# MCU_STM32F446RE.net
KiCad netlist of a schematic drawn in Altium Designer
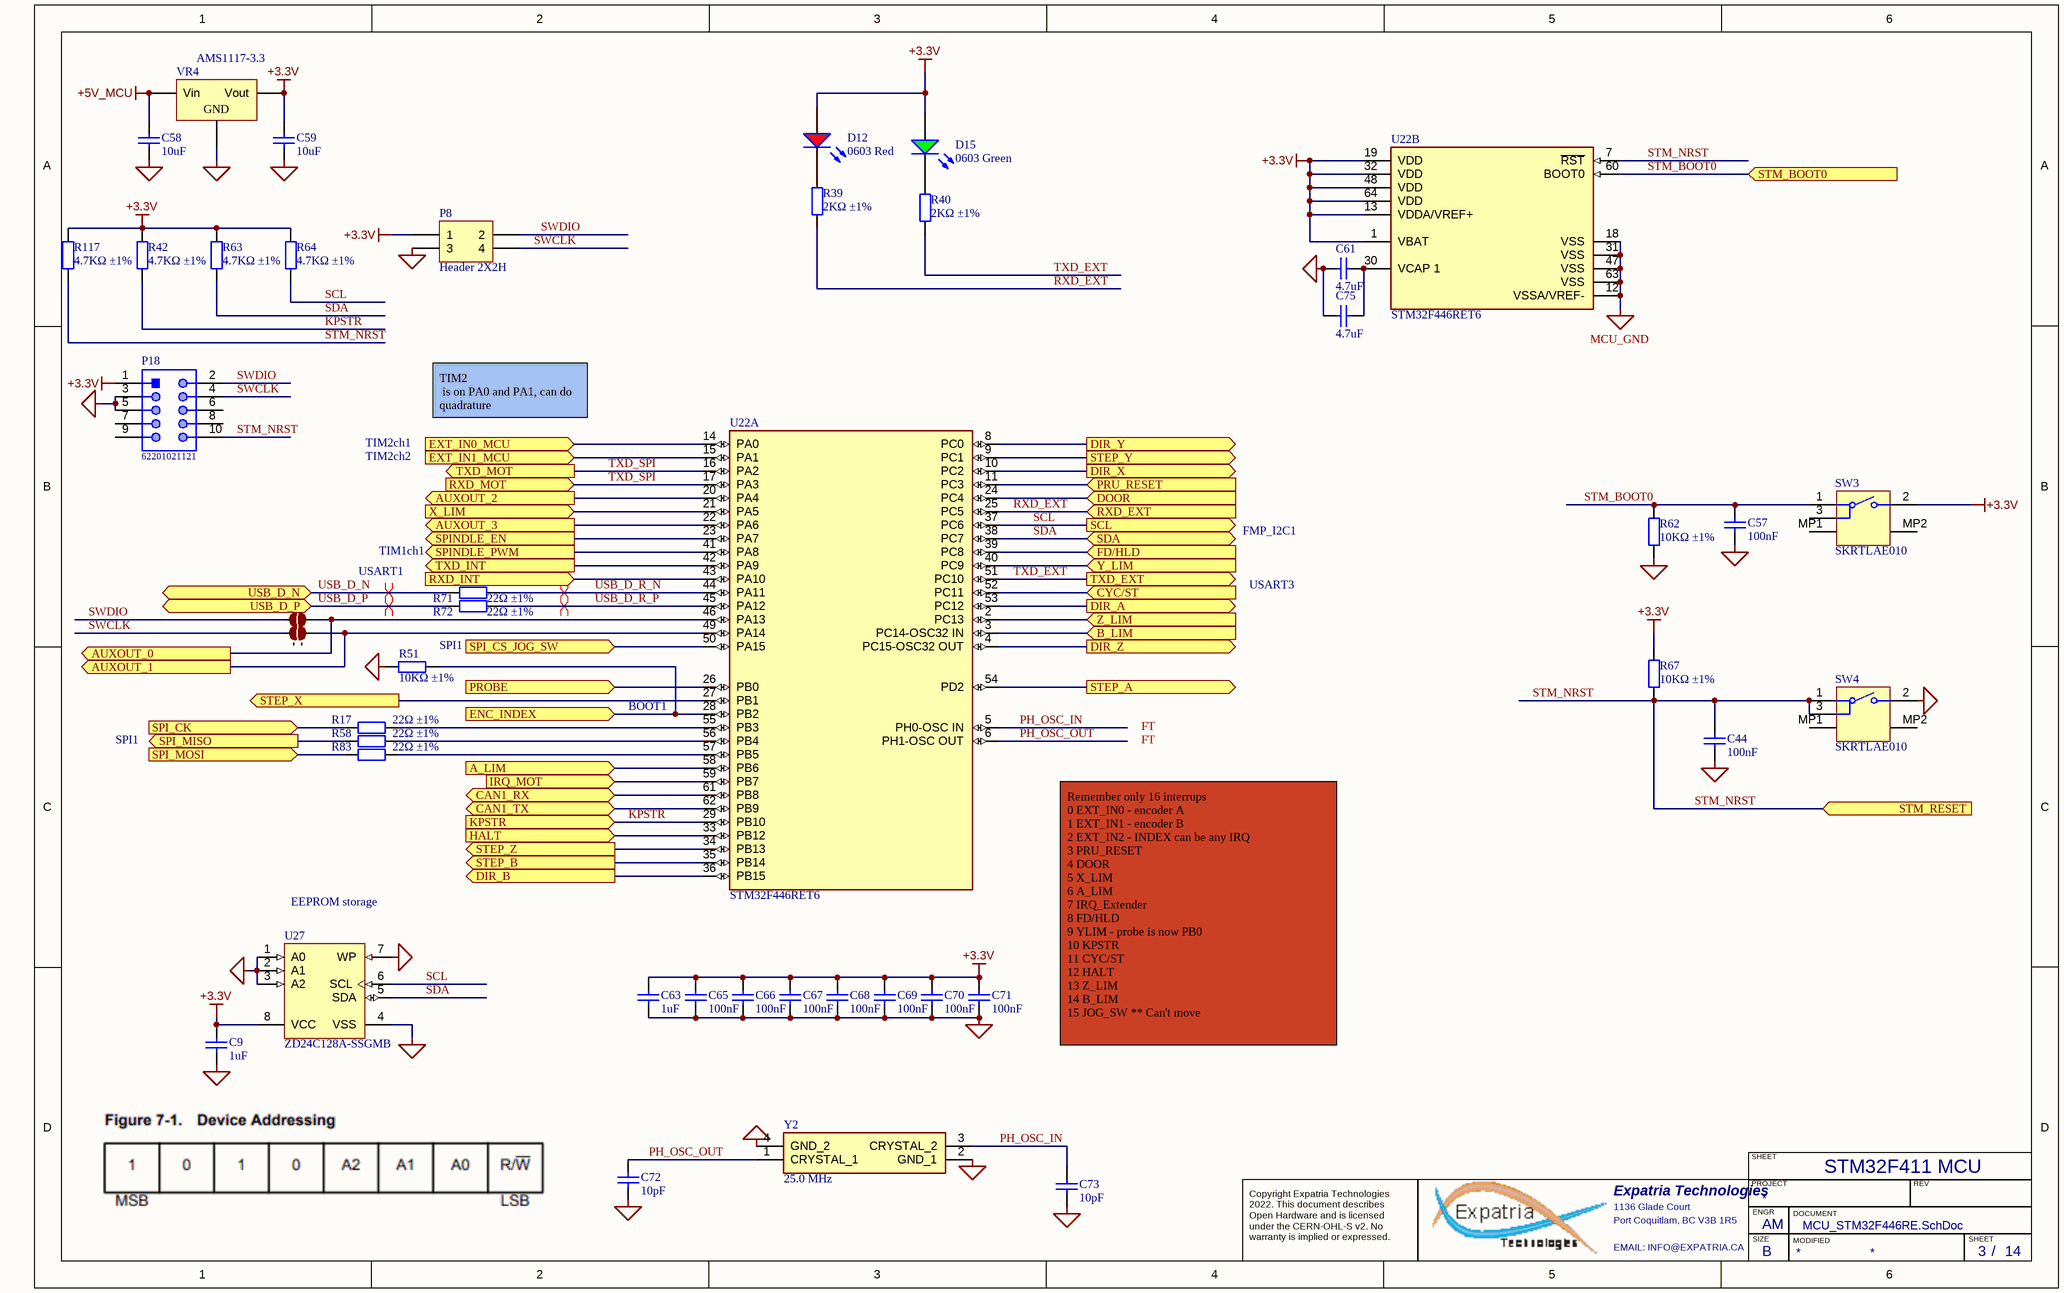
[diagram p0: MCU_STM32F446RE.SchDoc]

(export (version "E")
  (design (tool "Eeschema 10.0.6"))
  (components
    (comp (ref "C9")
      (value "1uF")
      (footprint "0603_C")
      (description "Chip capacitors")
      (fields
        (field (name "MANUFACTURER") "Samsung Electro-Mechanics")
        (field (name "PARTNUMBER") "CL10A105KB8NNNC")
      )
      (libsource (lib "Cap") (part "0603 1uF (105) 10% 50V"))
    )
    (comp (ref "C44")
      (value "100nF")
      (footprint "0603_C")
      (description "Chip capacitors")
      (fields (field (name "MANUFACTURER") "YAGEO") (field (name "PARTNUMBER") "CC0603KRX7R9BB104"))
      (libsource (lib "Cap") (part "0603 100nF (104) 10% 50V"))
    )
    (comp (ref "C57")
      (value "100nF")
      (footprint "0603_C")
      (description "Chip capacitors")
      (fields (field (name "MANUFACTURER") "YAGEO") (field (name "PARTNUMBER") "CC0603KRX7R9BB104"))
      (libsource (lib "Cap") (part "0603 100nF (104) 10% 50V"))
    )
    (comp (ref "C58")
      (value "10uF")
      (footprint "1206_C")
      (description "Chip capacitors")
      (fields
        (field (name "MANUFACTURER") "Samsung Electro-Mechanics")
        (field (name "PARTNUMBER") "CL31A106KBHNNNE")
      )
      (libsource (lib "Cap") (part "1206 10uF (106) 10% 50V"))
    )
    (comp (ref "C59")
      (value "10uF")
      (footprint "1206_C")
      (description "Chip capacitors")
      (fields
        (field (name "MANUFACTURER") "Samsung Electro-Mechanics")
        (field (name "PARTNUMBER") "CL31A106KBHNNNE")
      )
      (libsource (lib "Cap") (part "1206 10uF (106) 10% 50V"))
    )
    (comp (ref "C61")
      (value "4.7uF")
      (footprint "0603_C")
      (description "Chip capacitors")
      (fields
        (field (name "MANUFACTURER") "Samsung Electro-Mechanics")
        (field (name "PARTNUMBER") "CL10A475KO8NNNC")
      )
      (libsource (lib "Cap") (part "0603 4.7uF (475) 10% 16V"))
    )
    (comp (ref "C63")
      (value "1uF")
      (footprint "0603_C")
      (description "Chip capacitors")
      (fields
        (field (name "MANUFACTURER") "Samsung Electro-Mechanics")
        (field (name "PARTNUMBER") "CL10A105KB8NNNC")
      )
      (libsource (lib "Cap") (part "0603 1uF (105) 10% 50V"))
    )
    (comp (ref "C65")
      (value "100nF")
      (footprint "0603_C")
      (description "Chip capacitors")
      (fields (field (name "MANUFACTURER") "YAGEO") (field (name "PARTNUMBER") "CC0603KRX7R9BB104"))
      (libsource (lib "Cap") (part "0603 100nF (104) 10% 50V"))
    )
    (comp (ref "C66")
      (value "100nF")
      (footprint "0603_C")
      (description "Chip capacitors")
      (fields (field (name "MANUFACTURER") "YAGEO") (field (name "PARTNUMBER") "CC0603KRX7R9BB104"))
      (libsource (lib "Cap") (part "0603 100nF (104) 10% 50V"))
    )
    (comp (ref "C67")
      (value "100nF")
      (footprint "0603_C")
      (description "Chip capacitors")
      (fields (field (name "MANUFACTURER") "YAGEO") (field (name "PARTNUMBER") "CC0603KRX7R9BB104"))
      (libsource (lib "Cap") (part "0603 100nF (104) 10% 50V"))
    )
    (comp (ref "C68")
      (value "100nF")
      (footprint "0603_C")
      (description "Chip capacitors")
      (fields (field (name "MANUFACTURER") "YAGEO") (field (name "PARTNUMBER") "CC0603KRX7R9BB104"))
      (libsource (lib "Cap") (part "0603 100nF (104) 10% 50V"))
    )
    (comp (ref "C69")
      (value "100nF")
      (footprint "0603_C")
      (description "Chip capacitors")
      (fields (field (name "MANUFACTURER") "YAGEO") (field (name "PARTNUMBER") "CC0603KRX7R9BB104"))
      (libsource (lib "Cap") (part "0603 100nF (104) 10% 50V"))
    )
    (comp (ref "C70")
      (value "100nF")
      (footprint "0603_C")
      (description "Chip capacitors")
      (fields (field (name "MANUFACTURER") "YAGEO") (field (name "PARTNUMBER") "CC0603KRX7R9BB104"))
      (libsource (lib "Cap") (part "0603 100nF (104) 10% 50V"))
    )
    (comp (ref "C71")
      (value "100nF")
      (footprint "0603_C")
      (description "Chip capacitors")
      (fields (field (name "MANUFACTURER") "YAGEO") (field (name "PARTNUMBER") "CC0603KRX7R9BB104"))
      (libsource (lib "Cap") (part "0603 100nF (104) 10% 50V"))
    )
    (comp (ref "C72")
      (value "10pF")
      (footprint "0603_C")
      (description "Chip capacitors")
      (fields
        (field (name "MANUFACTURER") "Samsung Electro-Mechanics")
        (field (name "PARTNUMBER") "CL10C100JB8NNNC")
      )
      (libsource (lib "Cap") (part "0603 10pF (100) 5% 50V"))
    )
    (comp (ref "C73")
      (value "10pF")
      (footprint "0603_C")
      (description "Chip capacitors")
      (fields
        (field (name "MANUFACTURER") "Samsung Electro-Mechanics")
        (field (name "PARTNUMBER") "CL10C100JB8NNNC")
      )
      (libsource (lib "Cap") (part "0603 10pF (100) 5% 50V"))
    )
    (comp (ref "C75")
      (value "4.7uF")
      (footprint "0603_C")
      (description "Chip capacitors")
      (fields
        (field (name "MANUFACTURER") "Samsung Electro-Mechanics")
        (field (name "PARTNUMBER") "CL10A475KO8NNNC")
      )
      (libsource (lib "Cap") (part "0603 4.7uF (475) 10% 16V"))
    )
    (comp (ref "D12")
      (value "0603 Red")
      (footprint "0603_LED_S1")
      (description "LED")
      (libsource (lib "LED") (part "0603 LED Red"))
    )
    (comp (ref "D15")
      (value "0603 Green")
      (footprint "0603_LED_S1")
      (description "LED")
      (libsource (lib "LED") (part "0603 LED Green"))
    )
    (comp (ref "J10")
      (value "2 way net solder junction - Normally Open")
      (footprint "2waySolder_NO")
      (libsource (lib "PrintNC_GRBLHAL_Breakout") (part "2waySolderNO"))
    )
    (comp (ref "J11")
      (value "2 way net solder junction - Normally Open")
      (footprint "2waySolder_NO")
      (libsource (lib "PrintNC_GRBLHAL_Breakout") (part "2waySolderNO"))
    )
    (comp (ref "P8")
      (value "Header 2X2H")
      (footprint "HDR2X2H")
      (description "Header, 2-Pin, Dual row, Right Angle")
      (fields (field (name "PUBLISHER") "Altium Limited"))
      (libsource (lib "Miscellaneous Connectors") (part "Header 2X2H"))
    )
    (comp (ref "P18")
      (value "62201021121")
      (footprint "62201021121")
      (description "THT Vertical Pin Header WR-PHD, Pitch 1.27 mm, Dual Row, 10 pins")
      (fields (field (name "MANUFACTURER") "Wurth Elektronik") (field (name "PUBLISHER") "WurthElektronik"))
      (libsource (lib "Altium Content Vault") (part "WE-CN-2P-M-R10"))
    )
    (comp (ref "R17")
      (value "22Ω ±1%")
      (footprint "0603_R")
      (description "Chip resistor")
      (fields (field (name "MANUFACTURER") "Uniroyal Elec") (field (name "PARTNUMBER") "0603WAF220JT5E"))
      (libsource (lib "RES") (part "0603 22R (22R0) 1%"))
    )
    (comp (ref "R39")
      (value "2KΩ ±1%")
      (footprint "0603_R")
      (description "Chip resistor")
      (fields (field (name "MANUFACTURER") "Uniroyal Elec") (field (name "PARTNUMBER") "0603WAF2001T5E"))
      (libsource (lib "RES") (part "0603 2K (2001) 1%"))
    )
    (comp (ref "R40")
      (value "2KΩ ±1%")
      (footprint "0603_R")
      (description "Chip resistor")
      (fields (field (name "MANUFACTURER") "Uniroyal Elec") (field (name "PARTNUMBER") "0603WAF2001T5E"))
      (libsource (lib "RES") (part "0603 2K (2001) 1%"))
    )
    (comp (ref "R42")
      (value "4.7KΩ ±1%")
      (footprint "0603_R")
      (description "Chip resistor")
      (fields (field (name "MANUFACTURER") "Uniroyal Elec") (field (name "PARTNUMBER") "0603WAF4701T5E"))
      (libsource (lib "RES") (part "0603 4.7K (4701) 1%"))
    )
    (comp (ref "R51")
      (value "10KΩ ±1%")
      (footprint "0603_R")
      (description "Chip resistor")
      (fields (field (name "MANUFACTURER") "Uniroyal Elec") (field (name "PARTNUMBER") "0603WAF1002T5E"))
      (libsource (lib "") (part "0603 10K (1002) 1%_1"))
    )
    (comp (ref "R58")
      (value "22Ω ±1%")
      (footprint "0603_R")
      (description "Chip resistor")
      (fields (field (name "MANUFACTURER") "Uniroyal Elec") (field (name "PARTNUMBER") "0603WAF220JT5E"))
      (libsource (lib "RES") (part "0603 22R (22R0) 1%"))
    )
    (comp (ref "R62")
      (value "10KΩ ±1%")
      (footprint "0603_R")
      (description "Chip resistor")
      (fields (field (name "MANUFACTURER") "Uniroyal Elec") (field (name "PARTNUMBER") "0603WAF1002T5E"))
      (libsource (lib "RES") (part "0603 10K (1002) 1%"))
    )
    (comp (ref "R63")
      (value "4.7KΩ ±1%")
      (footprint "0603_R")
      (description "Chip resistor")
      (fields (field (name "MANUFACTURER") "Uniroyal Elec") (field (name "PARTNUMBER") "0603WAF4701T5E"))
      (libsource (lib "RES") (part "0603 4.7K (4701) 1%"))
    )
    (comp (ref "R64")
      (value "4.7KΩ ±1%")
      (footprint "0603_R")
      (description "Chip resistor")
      (fields (field (name "MANUFACTURER") "Uniroyal Elec") (field (name "PARTNUMBER") "0603WAF4701T5E"))
      (libsource (lib "RES") (part "0603 4.7K (4701) 1%"))
    )
    (comp (ref "R67")
      (value "10KΩ ±1%")
      (footprint "0603_R")
      (description "Chip resistor")
      (fields (field (name "MANUFACTURER") "Uniroyal Elec") (field (name "PARTNUMBER") "0603WAF1002T5E"))
      (libsource (lib "RES") (part "0603 10K (1002) 1%"))
    )
    (comp (ref "R71")
      (value "22Ω ±1%")
      (footprint "0603_R")
      (description "Chip resistor")
      (fields (field (name "MANUFACTURER") "Uniroyal Elec") (field (name "PARTNUMBER") "0603WAF220JT5E"))
      (libsource (lib "RES") (part "0603 22R (22R0) 1%"))
    )
    (comp (ref "R72")
      (value "22Ω ±1%")
      (footprint "0603_R")
      (description "Chip resistor")
      (fields (field (name "MANUFACTURER") "Uniroyal Elec") (field (name "PARTNUMBER") "0603WAF220JT5E"))
      (libsource (lib "RES") (part "0603 22R (22R0) 1%"))
    )
    (comp (ref "R83")
      (value "22Ω ±1%")
      (footprint "0603_R")
      (description "Chip resistor")
      (fields (field (name "MANUFACTURER") "Uniroyal Elec") (field (name "PARTNUMBER") "0603WAF220JT5E"))
      (libsource (lib "RES") (part "0603 22R (22R0) 1%"))
    )
    (comp (ref "R117")
      (value "4.7KΩ ±1%")
      (footprint "0603_R")
      (description "Chip resistor")
      (fields (field (name "MANUFACTURER") "Uniroyal Elec") (field (name "PARTNUMBER") "0603WAF4701T5E"))
      (libsource (lib "RES") (part "0603 4.7K (4701) 1%"))
    )
    (comp (ref "SW3")
      (value "SKRTLAE010")
      (footprint "ALPS-SKRTLAE010_V")
      (description "Side Push Type, 250 V, -40 to 90 degC, 3-Pin SMD, RoHS, Tape and Reel")
      (fields (field (name "MANUFACTURER") "ALPS"))
      (libsource (lib "Altium Content Vault") (part "SW_SPST-3_A"))
    )
    (comp (ref "SW4")
      (value "SKRTLAE010")
      (footprint "ALPS-SKRTLAE010_V")
      (description "Side Push Type, 250 V, -40 to 90 degC, 3-Pin SMD, RoHS, Tape and Reel")
      (fields (field (name "MANUFACTURER") "ALPS"))
      (libsource (lib "Altium Content Vault") (part "SW_SPST-3_A"))
    )
    (comp (ref "U22")
      (value "STM32F446RET6")
      (footprint "FP-LQFP64-5W-IPC_B")
      (description "IC MCU 32BIT 512KB FLASH 64LQFP")
      (fields
        (field (name "OCTOPART") "https://octopart.com/stm32f446ret6-stmicroelectronics-52642920")
        (field (name "MANUFACTURER") "STMicroelectronics")
      )
      (libsource (lib "Universal_CNC_Breakout") (part "STM32F446RET6"))
    )
    (comp (ref "U27")
      (value "ZD24C128A-SSGMB")
      (footprint "SOIC-SN8_L")
      (description "IC EEPROM 128KBIT I2C 8SOIC")
      (libsource (lib "PrintNC_GRBLHAL_Breakout") (part "MEM-SEEPROM-34AA02-IL8"))
    )
    (comp (ref "VR4")
      (value "AMS1117-3.3")
      (footprint "SOT-223")
      (description "Vout=3.3V 1A 72dB@(120Hz) (LDO)")
      (libsource (lib "LDO") (part "SOT-223 AMS1117-3.3"))
    )
    (comp (ref "Y2")
      (value "25.0 MHz")
      (footprint "SamacSys:YSX321SL")
      (description "Crystal or Oscillator")
      (fields (field (name "MANUFACTURER_PART_NUMBER") "X322525MSB4SI"))
      (libsource (lib "*") (part "YSX321SL"))
    )
  )
  (nets
    (net (code "1") (name "+3.3V") (class "Default")
      (node (ref "C59") (pin "2") (pinfunction "2_2") (pintype "passive"))
      (node (ref "C63") (pin "2") (pinfunction "2_2") (pintype "passive"))
      (node (ref "C65") (pin "2") (pinfunction "2_2") (pintype "passive"))
      (node (ref "C66") (pin "2") (pinfunction "2_2") (pintype "passive"))
      (node (ref "C67") (pin "2") (pinfunction "2_2") (pintype "passive"))
      (node (ref "C68") (pin "2") (pinfunction "2_2") (pintype "passive"))
      (node (ref "C69") (pin "2") (pinfunction "2_2") (pintype "passive"))
      (node (ref "C70") (pin "2") (pinfunction "2_2") (pintype "passive"))
      (node (ref "C71") (pin "2") (pinfunction "2_2") (pintype "passive"))
      (node (ref "C9") (pin "2") (pinfunction "2_2") (pintype "passive"))
      (node (ref "D12") (pin "A") (pinfunction "A_A") (pintype "passive"))
      (node (ref "D15") (pin "A") (pinfunction "A_A") (pintype "passive"))
      (node (ref "P18") (pin "1") (pinfunction "1_1") (pintype "passive"))
      (node (ref "P8") (pin "1") (pinfunction "1_1") (pintype "passive"))
      (node (ref "R117") (pin "2") (pinfunction "2_2") (pintype "passive"))
      (node (ref "R42") (pin "2") (pinfunction "2_2") (pintype "passive"))
      (node (ref "R63") (pin "2") (pinfunction "2_2") (pintype "passive"))
      (node (ref "R64") (pin "2") (pinfunction "2_2") (pintype "passive"))
      (node (ref "R67") (pin "1") (pinfunction "1_1") (pintype "passive"))
      (node (ref "SW3") (pin "2") (pinfunction "2_2") (pintype "passive"))
      (node (ref "U22") (pin "1") (pinfunction "VBAT_1") (pintype "power_in"))
      (node (ref "U22") (pin "13") (pinfunction "VDDA/VREF+_13") (pintype "power_in"))
      (node (ref "U22") (pin "19") (pinfunction "VDD_19") (pintype "power_in"))
      (node (ref "U22") (pin "32") (pinfunction "VDD_32") (pintype "power_in"))
      (node (ref "U22") (pin "48") (pinfunction "VDD_48") (pintype "power_in"))
      (node (ref "U22") (pin "64") (pinfunction "VDD_64") (pintype "power_in"))
      (node (ref "U27") (pin "8") (pinfunction "VCC_8") (pintype "power_in"))
      (node (ref "VR4") (pin "2") (pinfunction "Vout_2") (pintype "passive"))
    )
    (net (code "2") (name "+5V_MCU") (class "Default")
      (node (ref "C58") (pin "2") (pinfunction "2_2") (pintype "passive"))
      (node (ref "VR4") (pin "3") (pinfunction "Vin_3") (pintype "passive"))
    )
    (net (code "3") (name "/AUXOUT_0") (class "Default")
      (node (ref "J10") (pin "2") (pinfunction "2_2") (pintype "passive"))
      (node (ref "U22") (pin "46") (pinfunction "PA13_46") (pintype "bidirectional"))
    )
    (net (code "4") (name "/AUXOUT_1") (class "Default")
      (node (ref "J11") (pin "2") (pinfunction "2_2") (pintype "passive"))
      (node (ref "U22") (pin "49") (pinfunction "PA14_49") (pintype "bidirectional"))
    )
    (net (code "5") (name "/AUXOUT_2") (class "Default")
      (node (ref "U22") (pin "20") (pinfunction "PA4_20") (pintype "bidirectional"))
    )
    (net (code "6") (name "/AUXOUT_3") (class "Default")
      (node (ref "U22") (pin "22") (pinfunction "PA6_22") (pintype "bidirectional"))
    )
    (net (code "7") (name "/A_LIM") (class "Default")
      (node (ref "U22") (pin "58") (pinfunction "PB6_58") (pintype "bidirectional"))
    )
    (net (code "8") (name "/B_LIM") (class "Default")
      (node (ref "U22") (pin "3") (pinfunction "PC14-OSC32_IN_3") (pintype "bidirectional"))
    )
    (net (code "9") (name "/CAN1_RX") (class "Default")
      (node (ref "U22") (pin "61") (pinfunction "PB8_61") (pintype "bidirectional"))
    )
    (net (code "10") (name "/CAN1_TX") (class "Default")
      (node (ref "U22") (pin "62") (pinfunction "PB9_62") (pintype "bidirectional"))
    )
    (net (code "11") (name "/CYC{slash}ST") (class "Default")
      (node (ref "U22") (pin "52") (pinfunction "PC11_52") (pintype "bidirectional"))
    )
    (net (code "12") (name "/DIR_A") (class "Default")
      (node (ref "U22") (pin "53") (pinfunction "PC12_53") (pintype "bidirectional"))
    )
    (net (code "13") (name "/DIR_B") (class "Default")
      (node (ref "U22") (pin "36") (pinfunction "PB15_36") (pintype "bidirectional"))
    )
    (net (code "14") (name "/DIR_X") (class "Default")
      (node (ref "U22") (pin "10") (pinfunction "PC2_10") (pintype "bidirectional"))
    )
    (net (code "15") (name "/DIR_Y") (class "Default")
      (node (ref "U22") (pin "8") (pinfunction "PC0_8") (pintype "bidirectional"))
    )
    (net (code "16") (name "/DIR_Z") (class "Default")
      (node (ref "U22") (pin "4") (pinfunction "PC15-OSC32_OUT_4") (pintype "bidirectional"))
    )
    (net (code "17") (name "/DOOR") (class "Default")
      (node (ref "U22") (pin "24") (pinfunction "PC4_24") (pintype "bidirectional"))
    )
    (net (code "18") (name "/ENC_INDEX") (class "Default")
      (node (ref "R51") (pin "2") (pinfunction "2_2") (pintype "passive"))
      (node (ref "U22") (pin "28") (pinfunction "PB2_28") (pintype "bidirectional"))
    )
    (net (code "19") (name "/EXT_IN0_MCU") (class "Default")
      (node (ref "U22") (pin "14") (pinfunction "PA0_14") (pintype "bidirectional"))
    )
    (net (code "20") (name "/EXT_IN1_MCU") (class "Default")
      (node (ref "U22") (pin "15") (pinfunction "PA1_15") (pintype "bidirectional"))
    )
    (net (code "21") (name "/FD{slash}HLD") (class "Default")
      (node (ref "U22") (pin "39") (pinfunction "PC8_39") (pintype "bidirectional"))
    )
    (net (code "22") (name "/HALT") (class "Default")
      (node (ref "U22") (pin "33") (pinfunction "PB12_33") (pintype "bidirectional"))
    )
    (net (code "23") (name "/IRQ_MOT") (class "Default")
      (node (ref "U22") (pin "59") (pinfunction "PB7_59") (pintype "bidirectional"))
    )
    (net (code "24") (name "/KPSTR") (class "Default")
      (node (ref "R42") (pin "1") (pinfunction "1_1") (pintype "passive"))
      (node (ref "U22") (pin "29") (pinfunction "PB10_29") (pintype "bidirectional"))
    )
    (net (code "25") (name "/PH_OSC_IN") (class "Default")
      (node (ref "C73") (pin "2") (pinfunction "2_2") (pintype "passive"))
      (node (ref "U22") (pin "5") (pinfunction "PH0-OSC_IN_5") (pintype "bidirectional"))
      (node (ref "Y2") (pin "3") (pinfunction "CRYSTAL_2_3") (pintype "passive"))
    )
    (net (code "26") (name "/PH_OSC_OUT") (class "Default")
      (node (ref "C72") (pin "2") (pinfunction "2_2") (pintype "passive"))
      (node (ref "U22") (pin "6") (pinfunction "PH1-OSC_OUT_6") (pintype "bidirectional"))
      (node (ref "Y2") (pin "1") (pinfunction "CRYSTAL_1_1") (pintype "passive"))
    )
    (net (code "27") (name "/PROBE") (class "Default")
      (node (ref "U22") (pin "26") (pinfunction "PB0_26") (pintype "bidirectional"))
    )
    (net (code "28") (name "/PRU_RESET") (class "Default")
      (node (ref "U22") (pin "11") (pinfunction "PC3_11") (pintype "bidirectional"))
    )
    (net (code "29") (name "/RXD_EXT") (class "Default")
      (node (ref "R39") (pin "1") (pinfunction "1_1") (pintype "passive"))
      (node (ref "U22") (pin "25") (pinfunction "PC5_25") (pintype "bidirectional"))
    )
    (net (code "30") (name "/RXD_INT") (class "Default")
      (node (ref "U22") (pin "43") (pinfunction "PA10_43") (pintype "bidirectional"))
    )
    (net (code "31") (name "/SCL") (class "Default")
      (node (ref "R64") (pin "1") (pinfunction "1_1") (pintype "passive"))
      (node (ref "U22") (pin "37") (pinfunction "PC6_37") (pintype "bidirectional"))
      (node (ref "U27") (pin "6") (pinfunction "SCL_6") (pintype "input"))
    )
    (net (code "32") (name "/SDA") (class "Default")
      (node (ref "R63") (pin "1") (pinfunction "1_1") (pintype "passive"))
      (node (ref "U22") (pin "38") (pinfunction "PC7_38") (pintype "bidirectional"))
      (node (ref "U27") (pin "5") (pinfunction "SDA_5") (pintype "bidirectional"))
    )
    (net (code "33") (name "/SPINDLE_EN") (class "Default")
      (node (ref "U22") (pin "23") (pinfunction "PA7_23") (pintype "bidirectional"))
    )
    (net (code "34") (name "/SPINDLE_PWM") (class "Default")
      (node (ref "U22") (pin "41") (pinfunction "PA8_41") (pintype "bidirectional"))
    )
    (net (code "35") (name "/SPI_CK") (class "Default")
      (node (ref "R17") (pin "2") (pinfunction "2_2") (pintype "passive"))
    )
    (net (code "36") (name "/SPI_CS_JOG_SW") (class "Default")
      (node (ref "U22") (pin "50") (pinfunction "PA15_50") (pintype "bidirectional"))
    )
    (net (code "37") (name "/SPI_MISO") (class "Default")
      (node (ref "R58") (pin "2") (pinfunction "2_2") (pintype "passive"))
    )
    (net (code "38") (name "/SPI_MOSI") (class "Default")
      (node (ref "R83") (pin "2") (pinfunction "2_2") (pintype "passive"))
    )
    (net (code "39") (name "/STEP_A") (class "Default")
      (node (ref "U22") (pin "54") (pinfunction "PD2_54") (pintype "bidirectional"))
    )
    (net (code "40") (name "/STEP_B") (class "Default")
      (node (ref "U22") (pin "35") (pinfunction "PB14_35") (pintype "bidirectional"))
    )
    (net (code "41") (name "/STEP_X") (class "Default")
      (node (ref "U22") (pin "27") (pinfunction "PB1_27") (pintype "bidirectional"))
    )
    (net (code "42") (name "/STEP_Y") (class "Default")
      (node (ref "U22") (pin "9") (pinfunction "PC1_9") (pintype "bidirectional"))
    )
    (net (code "43") (name "/STEP_Z") (class "Default")
      (node (ref "U22") (pin "34") (pinfunction "PB13_34") (pintype "bidirectional"))
    )
    (net (code "44") (name "/STM_BOOT0") (class "Default")
      (node (ref "C57") (pin "2") (pinfunction "2_2") (pintype "passive"))
      (node (ref "R62") (pin "1") (pinfunction "1_1") (pintype "passive"))
      (node (ref "SW3") (pin "1") (pinfunction "1_1") (pintype "passive"))
      (node (ref "U22") (pin "60") (pinfunction "BOOT0_60") (pintype "input"))
    )
    (net (code "45") (name "/STM_NRST") (class "Default")
      (node (ref "C44") (pin "2") (pinfunction "2_2") (pintype "passive"))
      (node (ref "P18") (pin "10") (pinfunction "10_10") (pintype "passive"))
      (node (ref "R117") (pin "1") (pinfunction "1_1") (pintype "passive"))
      (node (ref "R67") (pin "2") (pinfunction "2_2") (pintype "passive"))
      (node (ref "SW4") (pin "1") (pinfunction "1_1") (pintype "passive"))
      (node (ref "SW4") (pin "3") (pinfunction "3_3") (pintype "passive"))
      (node (ref "U22") (pin "7") (pinfunction "~{RST}_7") (pintype "input"))
    )
    (net (code "46") (name "/SWCLK") (class "Default")
      (node (ref "J11") (pin "1") (pinfunction "1_1") (pintype "passive"))
      (node (ref "P18") (pin "4") (pinfunction "4_4") (pintype "passive"))
      (node (ref "P8") (pin "4") (pinfunction "4_4") (pintype "passive"))
    )
    (net (code "47") (name "/SWDIO") (class "Default")
      (node (ref "J10") (pin "1") (pinfunction "1_1") (pintype "passive"))
      (node (ref "P18") (pin "2") (pinfunction "2_2") (pintype "passive"))
      (node (ref "P8") (pin "2") (pinfunction "2_2") (pintype "passive"))
    )
    (net (code "48") (name "/TXD_EXT") (class "Default")
      (node (ref "R40") (pin "1") (pinfunction "1_1") (pintype "passive"))
      (node (ref "U22") (pin "51") (pinfunction "PC10_51") (pintype "bidirectional"))
    )
    (net (code "49") (name "/TXD_INT") (class "Default")
      (node (ref "U22") (pin "42") (pinfunction "PA9_42") (pintype "bidirectional"))
    )
    (net (code "50") (name "/TXD_SPI") (class "Default")
      (node (ref "U22") (pin "16") (pinfunction "PA2_16") (pintype "bidirectional"))
      (node (ref "U22") (pin "17") (pinfunction "PA3_17") (pintype "bidirectional"))
    )
    (net (code "51") (name "/USB_D_N") (class "Default")
      (node (ref "R71") (pin "2") (pinfunction "2_2") (pintype "passive"))
    )
    (net (code "52") (name "/USB_D_P") (class "Default")
      (node (ref "R72") (pin "2") (pinfunction "2_2") (pintype "passive"))
    )
    (net (code "53") (name "/USB_D_R_N") (class "Default")
      (node (ref "R71") (pin "1") (pinfunction "1_1") (pintype "passive"))
      (node (ref "U22") (pin "44") (pinfunction "PA11_44") (pintype "bidirectional"))
    )
    (net (code "54") (name "/USB_D_R_P") (class "Default")
      (node (ref "R72") (pin "1") (pinfunction "1_1") (pintype "passive"))
      (node (ref "U22") (pin "45") (pinfunction "PA12_45") (pintype "bidirectional"))
    )
    (net (code "55") (name "/X_LIM") (class "Default")
      (node (ref "U22") (pin "21") (pinfunction "PA5_21") (pintype "bidirectional"))
    )
    (net (code "56") (name "/Y_LIM") (class "Default")
      (node (ref "U22") (pin "40") (pinfunction "PC9_40") (pintype "bidirectional"))
    )
    (net (code "57") (name "/Z_LIM") (class "Default")
      (node (ref "U22") (pin "2") (pinfunction "PC13_2") (pintype "bidirectional"))
    )
    (net (code "58") (name "MCU_GND") (class "Default")
      (node (ref "C44") (pin "1") (pinfunction "1_1") (pintype "passive"))
      (node (ref "C57") (pin "1") (pinfunction "1_1") (pintype "passive"))
      (node (ref "C58") (pin "1") (pinfunction "1_1") (pintype "passive"))
      (node (ref "C59") (pin "1") (pinfunction "1_1") (pintype "passive"))
      (node (ref "C61") (pin "1") (pinfunction "1_1") (pintype "passive"))
      (node (ref "C63") (pin "1") (pinfunction "1_1") (pintype "passive"))
      (node (ref "C65") (pin "1") (pinfunction "1_1") (pintype "passive"))
      (node (ref "C66") (pin "1") (pinfunction "1_1") (pintype "passive"))
      (node (ref "C67") (pin "1") (pinfunction "1_1") (pintype "passive"))
      (node (ref "C68") (pin "1") (pinfunction "1_1") (pintype "passive"))
      (node (ref "C69") (pin "1") (pinfunction "1_1") (pintype "passive"))
      (node (ref "C70") (pin "1") (pinfunction "1_1") (pintype "passive"))
      (node (ref "C71") (pin "1") (pinfunction "1_1") (pintype "passive"))
      (node (ref "C72") (pin "1") (pinfunction "1_1") (pintype "passive"))
      (node (ref "C73") (pin "1") (pinfunction "1_1") (pintype "passive"))
      (node (ref "C75") (pin "1") (pinfunction "1_1") (pintype "passive"))
      (node (ref "C9") (pin "1") (pinfunction "1_1") (pintype "passive"))
      (node (ref "P18") (pin "3") (pinfunction "3_3") (pintype "passive"))
      (node (ref "P18") (pin "5") (pinfunction "5_5") (pintype "passive"))
      (node (ref "P8") (pin "3") (pinfunction "3_3") (pintype "passive"))
      (node (ref "R51") (pin "1") (pinfunction "1_1") (pintype "passive"))
      (node (ref "R62") (pin "2") (pinfunction "2_2") (pintype "passive"))
      (node (ref "SW4") (pin "2") (pinfunction "2_2") (pintype "passive"))
      (node (ref "U22") (pin "12") (pinfunction "VSSA/VREF-_12") (pintype "power_in"))
      (node (ref "U22") (pin "18") (pinfunction "VSS_18") (pintype "power_in"))
      (node (ref "U22") (pin "31") (pinfunction "VSS_31") (pintype "power_in"))
      (node (ref "U22") (pin "47") (pinfunction "VSS_47") (pintype "power_in"))
      (node (ref "U22") (pin "63") (pinfunction "VSS_63") (pintype "power_in"))
      (node (ref "U27") (pin "1") (pinfunction "A0_1") (pintype "input"))
      (node (ref "U27") (pin "2") (pinfunction "A1_2") (pintype "input"))
      (node (ref "U27") (pin "3") (pinfunction "A2_3") (pintype "input"))
      (node (ref "U27") (pin "4") (pinfunction "VSS_4") (pintype "power_in"))
      (node (ref "U27") (pin "7") (pinfunction "WP_7") (pintype "input"))
      (node (ref "VR4") (pin "1") (pinfunction "GND_1") (pintype "passive"))
      (node (ref "Y2") (pin "2") (pinfunction "GND_1_2") (pintype "passive"))
      (node (ref "Y2") (pin "4") (pinfunction "GND_2_4") (pintype "passive"))
    )
    (net (code "59") (name "Net-(D12-PadK)") (class "Default")
      (node (ref "D12") (pin "K") (pinfunction "K_K") (pintype "passive"))
      (node (ref "R39") (pin "2") (pinfunction "2_2") (pintype "passive"))
    )
    (net (code "60") (name "Net-(D15-PadK)") (class "Default")
      (node (ref "D15") (pin "K") (pinfunction "K_K") (pintype "passive"))
      (node (ref "R40") (pin "2") (pinfunction "2_2") (pintype "passive"))
    )
    (net (code "61") (name "Net-(U22A-PB3)") (class "Default")
      (node (ref "R17") (pin "1") (pinfunction "1_1") (pintype "passive"))
      (node (ref "U22") (pin "55") (pinfunction "PB3_55") (pintype "bidirectional"))
    )
    (net (code "62") (name "Net-(U22A-PB4)") (class "Default")
      (node (ref "R58") (pin "1") (pinfunction "1_1") (pintype "passive"))
      (node (ref "U22") (pin "56") (pinfunction "PB4_56") (pintype "bidirectional"))
    )
    (net (code "63") (name "Net-(U22A-PB5)") (class "Default")
      (node (ref "R83") (pin "1") (pinfunction "1_1") (pintype "passive"))
      (node (ref "U22") (pin "57") (pinfunction "PB5_57") (pintype "bidirectional"))
    )
    (net (code "64") (name "Net-(U22B-VCAP_1)") (class "Default")
      (node (ref "C61") (pin "2") (pinfunction "2_2") (pintype "passive"))
      (node (ref "C75") (pin "2") (pinfunction "2_2") (pintype "passive"))
      (node (ref "U22") (pin "30") (pinfunction "VCAP_1_30") (pintype "power_in"))
    )
    (net (code "65") (name "unconnected-(P18-Pad6)") (class "Default")
      (node (ref "P18") (pin "6") (pinfunction "6_6") (pintype "passive"))
    )
    (net (code "66") (name "unconnected-(P18-Pad7)") (class "Default")
      (node (ref "P18") (pin "7") (pinfunction "7_7") (pintype "passive"))
    )
    (net (code "67") (name "unconnected-(P18-Pad8)") (class "Default")
      (node (ref "P18") (pin "8") (pinfunction "8_8") (pintype "passive"))
    )
    (net (code "68") (name "unconnected-(P18-Pad9)") (class "Default")
      (node (ref "P18") (pin "9") (pinfunction "9_9") (pintype "passive"))
    )
    (net (code "69") (name "unconnected-(SW3-Pad3)") (class "Default")
      (node (ref "SW3") (pin "3") (pinfunction "3_3") (pintype "passive"))
    )
    (net (code "70") (name "unconnected-(SW3-PadMP1)") (class "Default")
      (node (ref "SW3") (pin "MP1") (pinfunction "MP1_MP1") (pintype "passive"))
    )
    (net (code "71") (name "unconnected-(SW3-PadMP2)") (class "Default")
      (node (ref "SW3") (pin "MP2") (pinfunction "MP2_MP2") (pintype "passive"))
    )
    (net (code "72") (name "unconnected-(SW4-PadMP1)") (class "Default")
      (node (ref "SW4") (pin "MP1") (pinfunction "MP1_MP1") (pintype "passive"))
    )
    (net (code "73") (name "unconnected-(SW4-PadMP2)") (class "Default")
      (node (ref "SW4") (pin "MP2") (pinfunction "MP2_MP2") (pintype "passive"))
    )
  )
)
